# DualJoyDivision.net
KiCad netlist of a schematic drawn in EAGLE
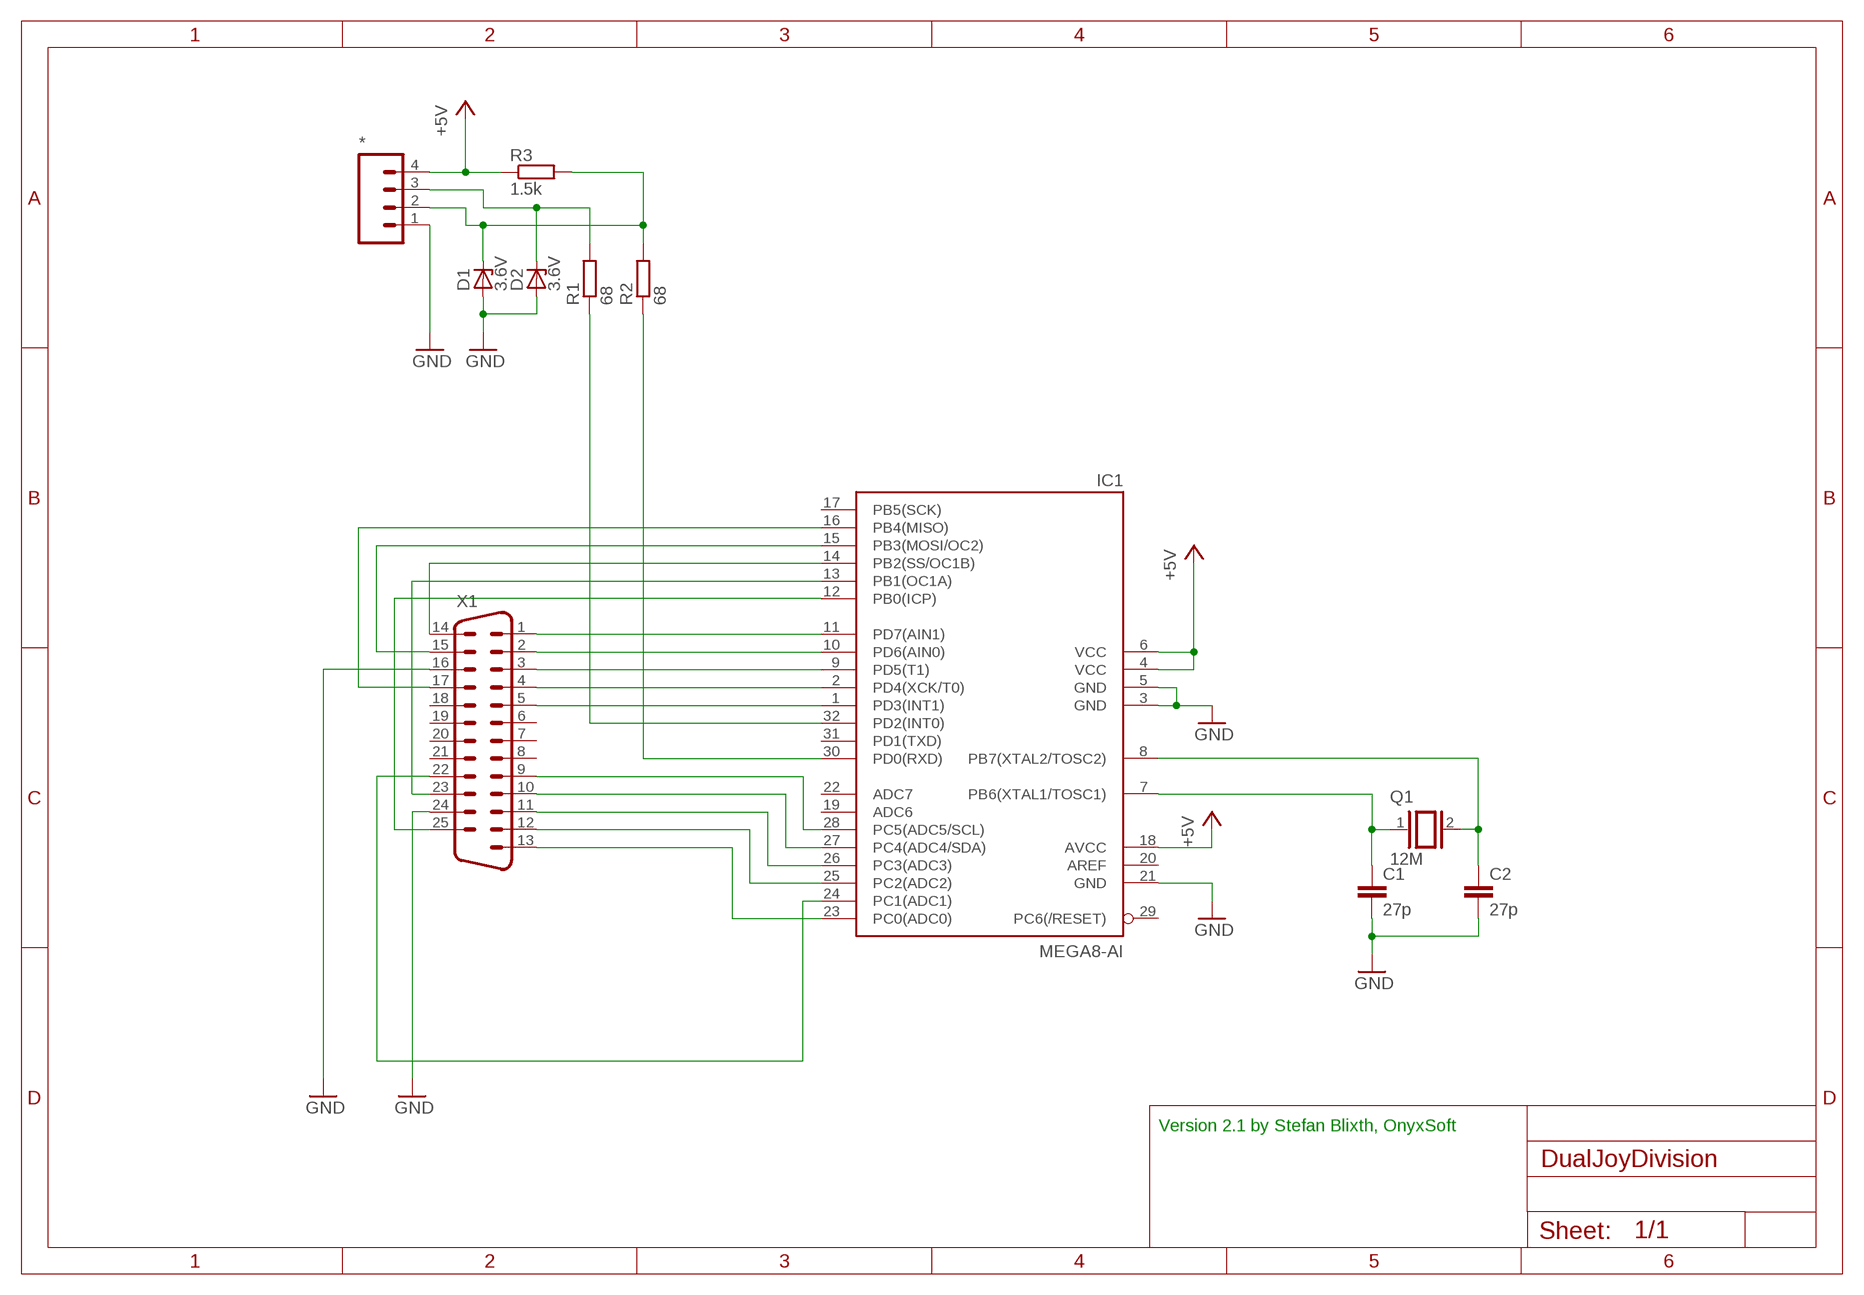
[diagram p0: schematic, sheet 1]

(export (version "E")
  (design (tool "Eeschema 10.0.6"))
  (components
    (comp (ref "*")
      (value "M04PTH")
      (footprint "eagle-import:1X04")
      (libsource (lib "eagle-import") (part "M04PTH"))
    )
    (comp (ref "C1")
      (value "27p")
      (footprint "eagle-import:C0805")
      (libsource (lib "eagle-import") (part "C-EUC0805"))
    )
    (comp (ref "C2")
      (value "27p")
      (footprint "eagle-import:C0805")
      (libsource (lib "eagle-import") (part "C-EUC0805"))
    )
    (comp (ref "D1")
      (value "3.6V")
      (footprint "eagle-import:SOD80C")
      (libsource (lib "eagle-import") (part "ZENER-DIODESOD80C"))
    )
    (comp (ref "D2")
      (value "3.6V")
      (footprint "eagle-import:SOD80C")
      (libsource (lib "eagle-import") (part "ZENER-DIODESOD80C"))
    )
    (comp (ref "IC1")
      (value "MEGA8-AI")
      (footprint "eagle-import:TQFP32-08")
      (fields (field (name "MPN") "ATMEGA8-16AU"))
      (libsource (lib "eagle-import") (part "MEGA8-AI"))
    )
    (comp (ref "Q1")
      (value "12M")
      (footprint "eagle-import:QS")
      (libsource (lib "eagle-import") (part "XTAL/S"))
    )
    (comp (ref "R1")
      (value "68")
      (footprint "eagle-import:M0805")
      (libsource (lib "eagle-import") (part "R-EU_M0805"))
    )
    (comp (ref "R2")
      (value "68")
      (footprint "eagle-import:M0805")
      (libsource (lib "eagle-import") (part "R-EU_M0805"))
    )
    (comp (ref "R3")
      (value "1.5k")
      (footprint "eagle-import:M0805")
      (libsource (lib "eagle-import") (part "R-EU_M0805"))
    )
    (comp (ref "X1")
      (value "DB25D")
      (footprint "eagle-import:M25D")
      (libsource (lib "eagle-import") (part "DB25D"))
    )
  )
  (nets
    (net (code "1") (name "+5V") (class "Default")
      (node (ref "*") (pin "4") (pinfunction "4_4") (pintype "passive"))
      (node (ref "IC1") (pin "18") (pinfunction "AVCC_18") (pintype "power_in"))
      (node (ref "IC1") (pin "4") (pinfunction "VCC_4") (pintype "power_in"))
      (node (ref "IC1") (pin "6") (pinfunction "VCC_6") (pintype "power_in"))
      (node (ref "R3") (pin "1") (pinfunction "1_1") (pintype "passive"))
    )
    (net (code "2") (name "GND") (class "Default")
      (node (ref "*") (pin "1") (pinfunction "1_1") (pintype "passive"))
      (node (ref "C1") (pin "2") (pinfunction "2_2") (pintype "passive"))
      (node (ref "C2") (pin "2") (pinfunction "2_2") (pintype "passive"))
      (node (ref "D1") (pin "A") (pinfunction "A_A") (pintype "passive"))
      (node (ref "D2") (pin "A") (pinfunction "A_A") (pintype "passive"))
      (node (ref "IC1") (pin "21") (pinfunction "GND_21") (pintype "power_in"))
      (node (ref "IC1") (pin "3") (pinfunction "GND_3") (pintype "power_in"))
      (node (ref "IC1") (pin "5") (pinfunction "GND_5") (pintype "power_in"))
      (node (ref "X1") (pin "16") (pinfunction "16_16") (pintype "passive"))
      (node (ref "X1") (pin "24") (pinfunction "24_24") (pintype "passive"))
    )
    (net (code "3") (name "Net-(*-Pad2)") (class "Default")
      (node (ref "*") (pin "2") (pinfunction "2_2") (pintype "passive"))
      (node (ref "D1") (pin "C") (pinfunction "C_C") (pintype "passive"))
      (node (ref "R2") (pin "2") (pinfunction "2_2") (pintype "passive"))
      (node (ref "R3") (pin "2") (pinfunction "2_2") (pintype "passive"))
    )
    (net (code "4") (name "Net-(*-Pad3)") (class "Default")
      (node (ref "*") (pin "3") (pinfunction "3_3") (pintype "passive"))
      (node (ref "D2") (pin "C") (pinfunction "C_C") (pintype "passive"))
      (node (ref "R1") (pin "2") (pinfunction "2_2") (pintype "passive"))
    )
    (net (code "5") (name "Net-(IC1-PB0(ICP))") (class "Default")
      (node (ref "IC1") (pin "12") (pinfunction "PB0(ICP)_12") (pintype "bidirectional"))
      (node (ref "X1") (pin "25") (pinfunction "25_25") (pintype "passive"))
    )
    (net (code "6") (name "Net-(IC1-PB1(OC1A))") (class "Default")
      (node (ref "IC1") (pin "13") (pinfunction "PB1(OC1A)_13") (pintype "bidirectional"))
      (node (ref "X1") (pin "23") (pinfunction "23_23") (pintype "passive"))
    )
    (net (code "7") (name "Net-(IC1-PB2(SS{slash}OC1B))") (class "Default")
      (node (ref "IC1") (pin "14") (pinfunction "PB2(SS/OC1B)_14") (pintype "bidirectional"))
      (node (ref "X1") (pin "14") (pinfunction "14_14") (pintype "passive"))
    )
    (net (code "8") (name "Net-(IC1-PB3(MOSI{slash}OC2))") (class "Default")
      (node (ref "IC1") (pin "15") (pinfunction "PB3(MOSI/OC2)_15") (pintype "bidirectional"))
      (node (ref "X1") (pin "15") (pinfunction "15_15") (pintype "passive"))
    )
    (net (code "9") (name "Net-(IC1-PB4(MISO))") (class "Default")
      (node (ref "IC1") (pin "16") (pinfunction "PB4(MISO)_16") (pintype "bidirectional"))
      (node (ref "X1") (pin "17") (pinfunction "17_17") (pintype "passive"))
    )
    (net (code "10") (name "Net-(IC1-PB6(XTAL1{slash}TOSC1))") (class "Default")
      (node (ref "C1") (pin "1") (pinfunction "1_1") (pintype "passive"))
      (node (ref "IC1") (pin "7") (pinfunction "PB6(XTAL1/TOSC1)_7") (pintype "bidirectional"))
      (node (ref "Q1") (pin "1") (pinfunction "1_1") (pintype "passive"))
    )
    (net (code "11") (name "Net-(IC1-PB7(XTAL2{slash}TOSC2))") (class "Default")
      (node (ref "C2") (pin "1") (pinfunction "1_1") (pintype "passive"))
      (node (ref "IC1") (pin "8") (pinfunction "PB7(XTAL2/TOSC2)_8") (pintype "bidirectional"))
      (node (ref "Q1") (pin "2") (pinfunction "2_2") (pintype "passive"))
    )
    (net (code "12") (name "Net-(IC1-PC0(ADC0))") (class "Default")
      (node (ref "IC1") (pin "23") (pinfunction "PC0(ADC0)_23") (pintype "bidirectional"))
      (node (ref "X1") (pin "13") (pinfunction "13_13") (pintype "passive"))
    )
    (net (code "13") (name "Net-(IC1-PC1(ADC1))") (class "Default")
      (node (ref "IC1") (pin "24") (pinfunction "PC1(ADC1)_24") (pintype "bidirectional"))
      (node (ref "X1") (pin "22") (pinfunction "22_22") (pintype "passive"))
    )
    (net (code "14") (name "Net-(IC1-PC2(ADC2))") (class "Default")
      (node (ref "IC1") (pin "25") (pinfunction "PC2(ADC2)_25") (pintype "bidirectional"))
      (node (ref "X1") (pin "12") (pinfunction "12_12") (pintype "passive"))
    )
    (net (code "15") (name "Net-(IC1-PC3(ADC3))") (class "Default")
      (node (ref "IC1") (pin "26") (pinfunction "PC3(ADC3)_26") (pintype "bidirectional"))
      (node (ref "X1") (pin "11") (pinfunction "11_11") (pintype "passive"))
    )
    (net (code "16") (name "Net-(IC1-PC4(ADC4{slash}SDA))") (class "Default")
      (node (ref "IC1") (pin "27") (pinfunction "PC4(ADC4/SDA)_27") (pintype "bidirectional"))
      (node (ref "X1") (pin "10") (pinfunction "10_10") (pintype "passive"))
    )
    (net (code "17") (name "Net-(IC1-PC5(ADC5{slash}SCL))") (class "Default")
      (node (ref "IC1") (pin "28") (pinfunction "PC5(ADC5/SCL)_28") (pintype "bidirectional"))
      (node (ref "X1") (pin "9") (pinfunction "9_9") (pintype "passive"))
    )
    (net (code "18") (name "Net-(IC1-PD0(RXD))") (class "Default")
      (node (ref "IC1") (pin "30") (pinfunction "PD0(RXD)_30") (pintype "bidirectional"))
      (node (ref "R2") (pin "1") (pinfunction "1_1") (pintype "passive"))
    )
    (net (code "19") (name "Net-(IC1-PD2(INT0))") (class "Default")
      (node (ref "IC1") (pin "32") (pinfunction "PD2(INT0)_32") (pintype "bidirectional"))
      (node (ref "R1") (pin "1") (pinfunction "1_1") (pintype "passive"))
    )
    (net (code "20") (name "Net-(IC1-PD3(INT1))") (class "Default")
      (node (ref "IC1") (pin "1") (pinfunction "PD3(INT1)_1") (pintype "bidirectional"))
      (node (ref "X1") (pin "5") (pinfunction "5_5") (pintype "passive"))
    )
    (net (code "21") (name "Net-(IC1-PD4(XCK{slash}T0))") (class "Default")
      (node (ref "IC1") (pin "2") (pinfunction "PD4(XCK/T0)_2") (pintype "bidirectional"))
      (node (ref "X1") (pin "4") (pinfunction "4_4") (pintype "passive"))
    )
    (net (code "22") (name "Net-(IC1-PD5(T1))") (class "Default")
      (node (ref "IC1") (pin "9") (pinfunction "PD5(T1)_9") (pintype "bidirectional"))
      (node (ref "X1") (pin "3") (pinfunction "3_3") (pintype "passive"))
    )
    (net (code "23") (name "Net-(IC1-PD6(AIN0))") (class "Default")
      (node (ref "IC1") (pin "10") (pinfunction "PD6(AIN0)_10") (pintype "bidirectional"))
      (node (ref "X1") (pin "2") (pinfunction "2_2") (pintype "passive"))
    )
    (net (code "24") (name "Net-(IC1-PD7(AIN1))") (class "Default")
      (node (ref "IC1") (pin "11") (pinfunction "PD7(AIN1)_11") (pintype "bidirectional"))
      (node (ref "X1") (pin "1") (pinfunction "1_1") (pintype "passive"))
    )
    (net (code "25") (name "unconnected-(IC1-ADC6-Pad19)") (class "Default")
      (node (ref "IC1") (pin "19") (pinfunction "ADC6_19") (pintype "bidirectional"))
    )
    (net (code "26") (name "unconnected-(IC1-ADC7-Pad22)") (class "Default")
      (node (ref "IC1") (pin "22") (pinfunction "ADC7_22") (pintype "bidirectional"))
    )
    (net (code "27") (name "unconnected-(IC1-AREF-Pad20)") (class "Default")
      (node (ref "IC1") (pin "20") (pinfunction "AREF_20") (pintype "passive"))
    )
    (net (code "28") (name "unconnected-(IC1-PB5(SCK)-Pad17)") (class "Default")
      (node (ref "IC1") (pin "17") (pinfunction "PB5(SCK)_17") (pintype "bidirectional"))
    )
    (net (code "29") (name "unconnected-(IC1-PC6({slash}RESET)-Pad29)") (class "Default")
      (node (ref "IC1") (pin "29") (pinfunction "PC6(/RESET)_29") (pintype "bidirectional"))
    )
    (net (code "30") (name "unconnected-(IC1-PD1(TXD)-Pad31)") (class "Default")
      (node (ref "IC1") (pin "31") (pinfunction "PD1(TXD)_31") (pintype "bidirectional"))
    )
    (net (code "31") (name "unconnected-(X1-Pad6)") (class "Default")
      (node (ref "X1") (pin "6") (pinfunction "6_6") (pintype "passive"))
    )
    (net (code "32") (name "unconnected-(X1-Pad7)") (class "Default")
      (node (ref "X1") (pin "7") (pinfunction "7_7") (pintype "passive"))
    )
    (net (code "33") (name "unconnected-(X1-Pad8)") (class "Default")
      (node (ref "X1") (pin "8") (pinfunction "8_8") (pintype "passive"))
    )
    (net (code "34") (name "unconnected-(X1-Pad18)") (class "Default")
      (node (ref "X1") (pin "18") (pinfunction "18_18") (pintype "passive"))
    )
    (net (code "35") (name "unconnected-(X1-Pad19)") (class "Default")
      (node (ref "X1") (pin "19") (pinfunction "19_19") (pintype "passive"))
    )
    (net (code "36") (name "unconnected-(X1-Pad20)") (class "Default")
      (node (ref "X1") (pin "20") (pinfunction "20_20") (pintype "passive"))
    )
    (net (code "37") (name "unconnected-(X1-Pad21)") (class "Default")
      (node (ref "X1") (pin "21") (pinfunction "21_21") (pintype "passive"))
    )
  )
)
